# GLCD.net
KiCad netlist of a schematic drawn in Altium Designer
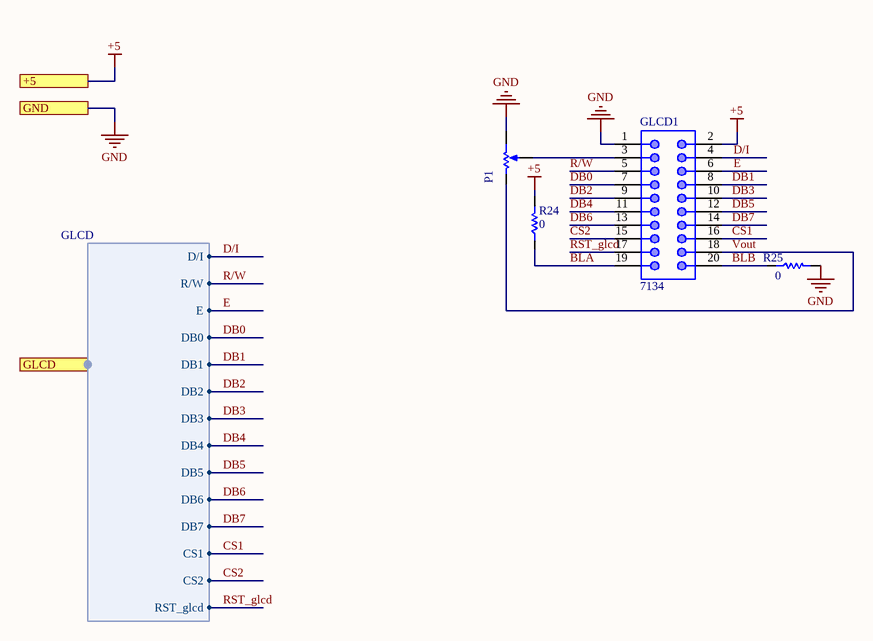
[diagram p0: GLCD.SchDoc]

(export (version "E")
  (design (tool "Eeschema 10.0.6"))
  (components
    (comp (ref "GLCD1")
      (value "10x2")
      (footprint "BOX-HDR-10X2-2.54mm-S")
      (description "Male Box Header, 20 pins")
      (fields (field (name "INFLOW") "7134") (field (name "VALIDATION") "NT"))
      (libsource (lib "aKaReZa") (part "Con_IDC_10x2"))
    )
    (comp (ref "P1")
      (value "10K")
      (footprint "Multi turn 01")
      (description "Multi Turn")
      (fields (field (name "VALIDATION") "Valid"))
      (libsource (lib "aKaReZa") (part "Res_Multi"))
    )
    (comp (ref "R24")
      (value "0")
      (footprint "RES 1206 (3216X08L)")
      (description "Resistor")
      (fields (field (name "VALIDATION") "Valid"))
      (libsource (lib "aKaReZa") (part "Res_SMD_1206"))
    )
    (comp (ref "R25")
      (value "0")
      (footprint "RES 1206 (3216X08L)")
      (description "Resistor")
      (fields (field (name "VALIDATION") "Valid"))
      (libsource (lib "aKaReZa") (part "Res_SMD_1206"))
    )
  )
  (nets
    (net (code "2") (name "+5") (class "Default")
      (node (ref "GLCD1") (pin "2") (pinfunction "2_2") (pintype "passive"))
      (node (ref "R24") (pin "2") (pinfunction "2_2") (pintype "passive"))
    )
    (net (code "3") (name "/BLA") (class "Default")
      (node (ref "GLCD1") (pin "19") (pinfunction "19_19") (pintype "passive"))
      (node (ref "R24") (pin "1") (pinfunction "1_1") (pintype "passive"))
    )
    (net (code "4") (name "/BLB") (class "Default")
      (node (ref "GLCD1") (pin "20") (pinfunction "20_20") (pintype "passive"))
      (node (ref "R25") (pin "1") (pinfunction "1_1") (pintype "passive"))
    )
    (net (code "5") (name "/CS1") (class "Default")
      (node (ref "GLCD1") (pin "16") (pinfunction "16_16") (pintype "passive"))
    )
    (net (code "6") (name "/CS2") (class "Default")
      (node (ref "GLCD1") (pin "15") (pinfunction "15_15") (pintype "passive"))
    )
    (net (code "7") (name "/DB0") (class "Default")
      (node (ref "GLCD1") (pin "7") (pinfunction "7_7") (pintype "passive"))
    )
    (net (code "8") (name "/DB1") (class "Default")
      (node (ref "GLCD1") (pin "8") (pinfunction "8_8") (pintype "passive"))
    )
    (net (code "9") (name "/DB2") (class "Default")
      (node (ref "GLCD1") (pin "9") (pinfunction "9_9") (pintype "passive"))
    )
    (net (code "10") (name "/DB3") (class "Default")
      (node (ref "GLCD1") (pin "10") (pinfunction "10_10") (pintype "passive"))
    )
    (net (code "11") (name "/DB4") (class "Default")
      (node (ref "GLCD1") (pin "11") (pinfunction "11_11") (pintype "passive"))
    )
    (net (code "12") (name "/DB5") (class "Default")
      (node (ref "GLCD1") (pin "12") (pinfunction "12_12") (pintype "passive"))
    )
    (net (code "13") (name "/DB6") (class "Default")
      (node (ref "GLCD1") (pin "13") (pinfunction "13_13") (pintype "passive"))
    )
    (net (code "14") (name "/DB7") (class "Default")
      (node (ref "GLCD1") (pin "14") (pinfunction "14_14") (pintype "passive"))
    )
    (net (code "15") (name "/D{slash}I") (class "Default")
      (node (ref "GLCD1") (pin "4") (pinfunction "4_4") (pintype "passive"))
    )
    (net (code "16") (name "/E") (class "Default")
      (node (ref "GLCD1") (pin "6") (pinfunction "6_6") (pintype "passive"))
    )
    (net (code "17") (name "/RST_glcd") (class "Default")
      (node (ref "GLCD1") (pin "17") (pinfunction "17_17") (pintype "passive"))
    )
    (net (code "18") (name "/R{slash}W") (class "Default")
      (node (ref "GLCD1") (pin "5") (pinfunction "5_5") (pintype "passive"))
    )
    (net (code "19") (name "/Vout") (class "Default")
      (node (ref "GLCD1") (pin "18") (pinfunction "18_18") (pintype "passive"))
      (node (ref "P1") (pin "3") (pinfunction "1_3") (pintype "passive"))
    )
    (net (code "21") (name "GND") (class "Default")
      (node (ref "GLCD1") (pin "1") (pinfunction "1_1") (pintype "passive"))
      (node (ref "P1") (pin "1") (pinfunction "3_1") (pintype "passive"))
      (node (ref "R25") (pin "2") (pinfunction "2_2") (pintype "passive"))
    )
    (net (code "22") (name "Net-(GLCD1-Pad3)") (class "Default")
      (node (ref "GLCD1") (pin "3") (pinfunction "3_3") (pintype "passive"))
      (node (ref "P1") (pin "2") (pinfunction "2_2") (pintype "passive"))
    )
  )
)
